# GLCD.net
KiCad netlist of a schematic drawn in Altium Designer
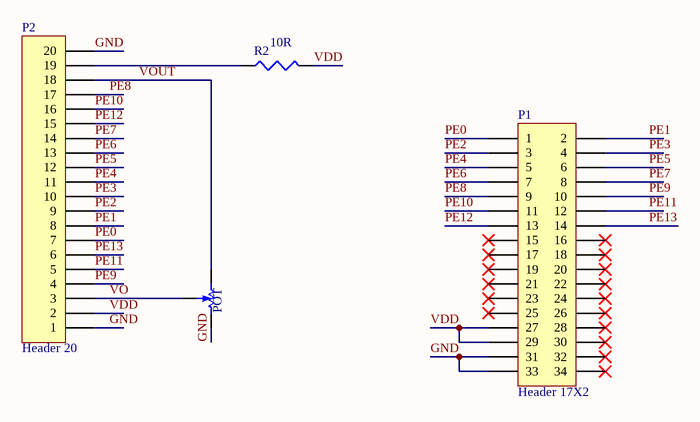
[diagram p0: GLCD.SchDoc]

(export (version "E")
  (design (tool "Eeschema 10.0.6"))
  (components
    (comp (ref "P1")
      (value "Header 17X2")
      (footprint "HDR2X17")
      (description "Header, 17-Pin, Dual row")
      (fields (field (name "PUBLISHER") "Altium Limited"))
      (libsource (lib "Miscellaneous Connectors") (part "Header 17X2"))
    )
    (comp (ref "P2")
      (value "Header 20")
      (footprint "small_header")
      (description "Header, 20-Pin")
      (fields (field (name "PUBLISHER") "Altium Limited"))
      (libsource (lib "Miscellaneous Connectors") (part "Header 20"))
    )
    (comp (ref "POT")
      (value "RPot SM")
      (footprint "pot")
      (description "Square Trimming Potentiometer")
      (fields (field (name "PUBLISHER") "Altium Limited"))
      (libsource (lib "Miscellaneous Devices") (part "RPot SM"))
    )
    (comp (ref "R2")
      (value "10R")
      (footprint "1206")
      (description "Resistor")
      (fields (field (name "Comment") "Res3") (field (name "PUBLISHER") "Altium Limited"))
      (libsource (lib "Miscellaneous Devices") (part "Res3"))
    )
  )
  (nets
    (net (code "1") (name "/GND") (class "Default")
      (node (ref "P1") (pin "31") (pinfunction "31_31") (pintype "passive"))
      (node (ref "P1") (pin "33") (pinfunction "33_33") (pintype "passive"))
      (node (ref "P2") (pin "1") (pinfunction "1_1") (pintype "passive"))
      (node (ref "P2") (pin "20") (pinfunction "20_20") (pintype "passive"))
      (node (ref "POT") (pin "CW") (pinfunction "+_CW") (pintype "passive"))
    )
    (net (code "2") (name "/PE0") (class "Default")
      (node (ref "P1") (pin "1") (pinfunction "1_1") (pintype "passive"))
      (node (ref "P2") (pin "7") (pinfunction "7_7") (pintype "passive"))
    )
    (net (code "3") (name "/PE1") (class "Default")
      (node (ref "P1") (pin "2") (pinfunction "2_2") (pintype "passive"))
      (node (ref "P2") (pin "8") (pinfunction "8_8") (pintype "passive"))
    )
    (net (code "4") (name "/PE2") (class "Default")
      (node (ref "P1") (pin "3") (pinfunction "3_3") (pintype "passive"))
      (node (ref "P2") (pin "9") (pinfunction "9_9") (pintype "passive"))
    )
    (net (code "5") (name "/PE3") (class "Default")
      (node (ref "P1") (pin "4") (pinfunction "4_4") (pintype "passive"))
      (node (ref "P2") (pin "10") (pinfunction "10_10") (pintype "passive"))
    )
    (net (code "6") (name "/PE4") (class "Default")
      (node (ref "P1") (pin "5") (pinfunction "5_5") (pintype "passive"))
      (node (ref "P2") (pin "11") (pinfunction "11_11") (pintype "passive"))
    )
    (net (code "7") (name "/PE5") (class "Default")
      (node (ref "P1") (pin "6") (pinfunction "6_6") (pintype "passive"))
      (node (ref "P2") (pin "12") (pinfunction "12_12") (pintype "passive"))
    )
    (net (code "8") (name "/PE6") (class "Default")
      (node (ref "P1") (pin "7") (pinfunction "7_7") (pintype "passive"))
      (node (ref "P2") (pin "13") (pinfunction "13_13") (pintype "passive"))
    )
    (net (code "9") (name "/PE7") (class "Default")
      (node (ref "P1") (pin "8") (pinfunction "8_8") (pintype "passive"))
      (node (ref "P2") (pin "14") (pinfunction "14_14") (pintype "passive"))
    )
    (net (code "10") (name "/PE8") (class "Default")
      (node (ref "P1") (pin "9") (pinfunction "9_9") (pintype "passive"))
      (node (ref "P2") (pin "17") (pinfunction "17_17") (pintype "passive"))
    )
    (net (code "11") (name "/PE9") (class "Default")
      (node (ref "P1") (pin "10") (pinfunction "10_10") (pintype "passive"))
      (node (ref "P2") (pin "4") (pinfunction "4_4") (pintype "passive"))
    )
    (net (code "12") (name "/PE10") (class "Default")
      (node (ref "P1") (pin "11") (pinfunction "11_11") (pintype "passive"))
      (node (ref "P2") (pin "16") (pinfunction "16_16") (pintype "passive"))
    )
    (net (code "13") (name "/PE11") (class "Default")
      (node (ref "P1") (pin "12") (pinfunction "12_12") (pintype "passive"))
      (node (ref "P2") (pin "5") (pinfunction "5_5") (pintype "passive"))
    )
    (net (code "14") (name "/PE12") (class "Default")
      (node (ref "P1") (pin "13") (pinfunction "13_13") (pintype "passive"))
      (node (ref "P2") (pin "15") (pinfunction "15_15") (pintype "passive"))
    )
    (net (code "15") (name "/PE13") (class "Default")
      (node (ref "P1") (pin "14") (pinfunction "14_14") (pintype "passive"))
      (node (ref "P2") (pin "6") (pinfunction "6_6") (pintype "passive"))
    )
    (net (code "16") (name "/VDD") (class "Default")
      (node (ref "P1") (pin "27") (pinfunction "27_27") (pintype "passive"))
      (node (ref "P1") (pin "29") (pinfunction "29_29") (pintype "passive"))
      (node (ref "P2") (pin "2") (pinfunction "2_2") (pintype "passive"))
      (node (ref "R2") (pin "2") (pinfunction "2_2") (pintype "passive"))
    )
    (net (code "17") (name "/VO") (class "Default")
      (node (ref "P2") (pin "3") (pinfunction "3_3") (pintype "passive"))
      (node (ref "POT") (pin "W") (pinfunction "W_W") (pintype "passive"))
    )
    (net (code "18") (name "/VOUT") (class "Default")
      (node (ref "P2") (pin "18") (pinfunction "18_18") (pintype "passive"))
      (node (ref "POT") (pin "CCW") (pinfunction "-_CCW") (pintype "passive"))
    )
    (net (code "19") (name "Net-(P2-Pad19)") (class "Default")
      (node (ref "P2") (pin "19") (pinfunction "19_19") (pintype "passive"))
      (node (ref "R2") (pin "1") (pinfunction "1_1") (pintype "passive"))
    )
    (net (code "20") (name "unconnected-(P1-Pad15)") (class "Default")
      (node (ref "P1") (pin "15") (pinfunction "15_15") (pintype "passive+no_connect"))
    )
    (net (code "21") (name "unconnected-(P1-Pad16)") (class "Default")
      (node (ref "P1") (pin "16") (pinfunction "16_16") (pintype "passive+no_connect"))
    )
    (net (code "22") (name "unconnected-(P1-Pad17)") (class "Default")
      (node (ref "P1") (pin "17") (pinfunction "17_17") (pintype "passive+no_connect"))
    )
    (net (code "23") (name "unconnected-(P1-Pad18)") (class "Default")
      (node (ref "P1") (pin "18") (pinfunction "18_18") (pintype "passive+no_connect"))
    )
    (net (code "24") (name "unconnected-(P1-Pad19)") (class "Default")
      (node (ref "P1") (pin "19") (pinfunction "19_19") (pintype "passive+no_connect"))
    )
    (net (code "25") (name "unconnected-(P1-Pad20)") (class "Default")
      (node (ref "P1") (pin "20") (pinfunction "20_20") (pintype "passive+no_connect"))
    )
    (net (code "26") (name "unconnected-(P1-Pad21)") (class "Default")
      (node (ref "P1") (pin "21") (pinfunction "21_21") (pintype "passive+no_connect"))
    )
    (net (code "27") (name "unconnected-(P1-Pad22)") (class "Default")
      (node (ref "P1") (pin "22") (pinfunction "22_22") (pintype "passive+no_connect"))
    )
    (net (code "28") (name "unconnected-(P1-Pad23)") (class "Default")
      (node (ref "P1") (pin "23") (pinfunction "23_23") (pintype "passive+no_connect"))
    )
    (net (code "29") (name "unconnected-(P1-Pad24)") (class "Default")
      (node (ref "P1") (pin "24") (pinfunction "24_24") (pintype "passive+no_connect"))
    )
    (net (code "30") (name "unconnected-(P1-Pad25)") (class "Default")
      (node (ref "P1") (pin "25") (pinfunction "25_25") (pintype "passive+no_connect"))
    )
    (net (code "31") (name "unconnected-(P1-Pad26)") (class "Default")
      (node (ref "P1") (pin "26") (pinfunction "26_26") (pintype "passive+no_connect"))
    )
    (net (code "32") (name "unconnected-(P1-Pad28)") (class "Default")
      (node (ref "P1") (pin "28") (pinfunction "28_28") (pintype "passive+no_connect"))
    )
    (net (code "33") (name "unconnected-(P1-Pad30)") (class "Default")
      (node (ref "P1") (pin "30") (pinfunction "30_30") (pintype "passive+no_connect"))
    )
    (net (code "34") (name "unconnected-(P1-Pad32)") (class "Default")
      (node (ref "P1") (pin "32") (pinfunction "32_32") (pintype "passive+no_connect"))
    )
    (net (code "35") (name "unconnected-(P1-Pad34)") (class "Default")
      (node (ref "P1") (pin "34") (pinfunction "34_34") (pintype "passive+no_connect"))
    )
  )
)
